# TOMO.net
KiCad netlist of a schematic drawn in EAGLE
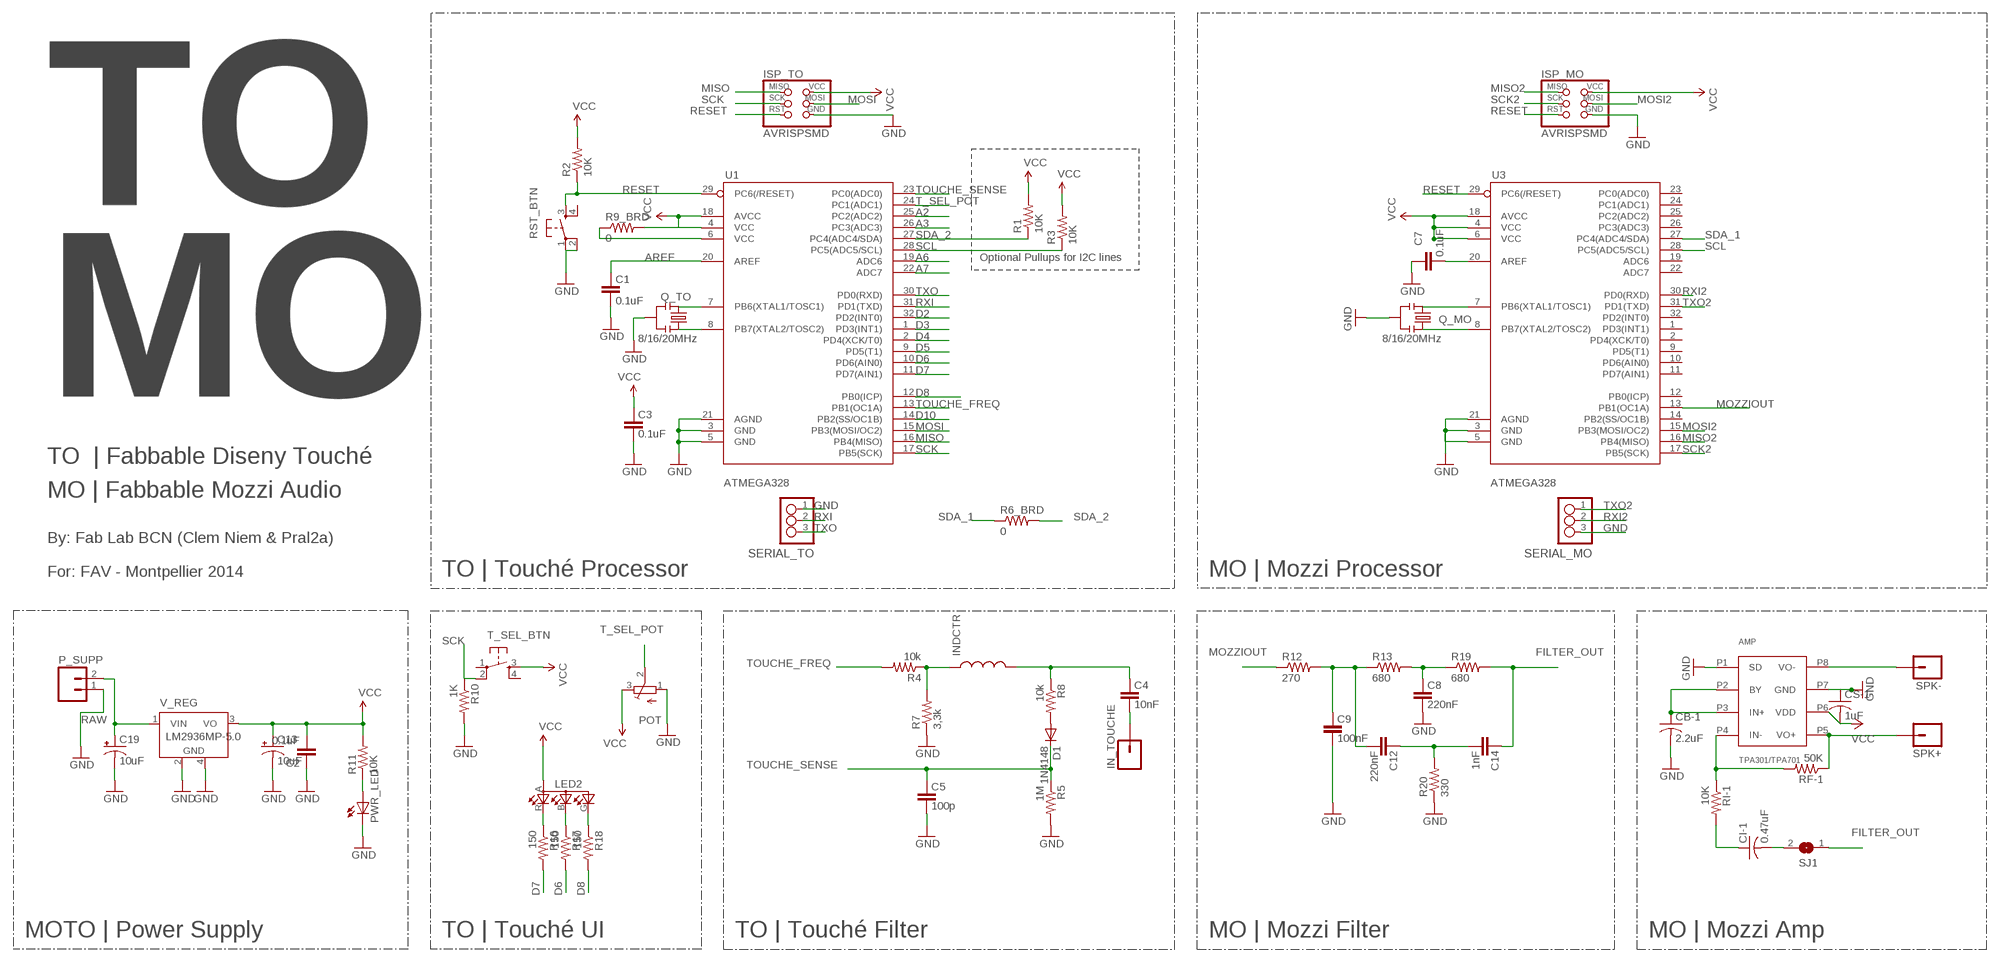
[diagram p0: schematic, sheet 1]

(export (version "E")
  (design (tool "Eeschema 10.0.6"))
  (components
    (comp (ref "AMP")
      (value "TPA301/TPA701")
      (footprint "eagle-import:SOIC8")
      (libsource (lib "eagle-import") (part "TPA301/TPA701"))
    )
    (comp (ref "C1")
      (value "0.1uF")
      (footprint "eagle-import:1206")
      (libsource (lib "eagle-import") (part "CAP1206"))
    )
    (comp (ref "C2")
      (value "0.1uF")
      (footprint "eagle-import:1206")
      (libsource (lib "eagle-import") (part "CAP1206"))
    )
    (comp (ref "C3")
      (value "0.1uF")
      (footprint "eagle-import:1206")
      (libsource (lib "eagle-import") (part "CAP1206"))
    )
    (comp (ref "C4")
      (value "10nF")
      (footprint "eagle-import:1206")
      (libsource (lib "eagle-import") (part "CAP1206"))
    )
    (comp (ref "C5")
      (value "100p")
      (footprint "eagle-import:1206")
      (libsource (lib "eagle-import") (part "CAP1206"))
    )
    (comp (ref "C7")
      (value "0.1uF")
      (footprint "eagle-import:1206")
      (libsource (lib "eagle-import") (part "CAP1206"))
    )
    (comp (ref "C8")
      (value "220nF")
      (footprint "eagle-import:1206")
      (libsource (lib "eagle-import") (part "CAP1206"))
    )
    (comp (ref "C9")
      (value "100nF")
      (footprint "eagle-import:1206")
      (libsource (lib "eagle-import") (part "CAP1206"))
    )
    (comp (ref "C12")
      (value "220nF")
      (footprint "eagle-import:1206")
      (libsource (lib "eagle-import") (part "CAP1206"))
    )
    (comp (ref "C13")
      (value "10uF")
      (footprint "eagle-import:EIA3216")
      (libsource (lib "eagle-import") (part "CAP_POL1206"))
    )
    (comp (ref "C14")
      (value "1nF")
      (footprint "eagle-import:1206")
      (libsource (lib "eagle-import") (part "CAP1206"))
    )
    (comp (ref "C19")
      (value "10uF")
      (footprint "eagle-import:EIA3216")
      (libsource (lib "eagle-import") (part "CAP_POL1206"))
    )
    (comp (ref "CB-1")
      (value "2.2uF")
      (footprint "eagle-import:C1206")
      (libsource (lib "eagle-import") (part "C-USC1206"))
    )
    (comp (ref "CI-1")
      (value "0.47uF")
      (footprint "eagle-import:C1206")
      (libsource (lib "eagle-import") (part "C-USC1206"))
    )
    (comp (ref "CS-1")
      (value "1uF")
      (footprint "eagle-import:C1206")
      (libsource (lib "eagle-import") (part "C-USC1206"))
    )
    (comp (ref "D1")
      (value "1N4148")
      (footprint "eagle-import:SOD123")
      (libsource (lib "eagle-import") (part "DIODESOD123"))
    )
    (comp (ref "INDCTR")
      (value "INDUCTOR")
      (footprint "eagle-import:CDRH3D28")
      (libsource (lib "eagle-import") (part "INDUCTOR"))
    )
    (comp (ref "IN_TOUCHE")
      (value "M01PTH")
      (footprint "eagle-import:1X01")
      (libsource (lib "eagle-import") (part "M01PTH"))
    )
    (comp (ref "ISP_MO")
      (value "AVRISPSMD")
      (footprint "eagle-import:2X03SMD")
      (libsource (lib "eagle-import") (part "AVRISPSMD"))
    )
    (comp (ref "ISP_TO")
      (value "AVRISPSMD")
      (footprint "eagle-import:2X03SMD")
      (libsource (lib "eagle-import") (part "AVRISPSMD"))
    )
    (comp (ref "LED2")
      (value "LEDRGBOLD")
      (footprint "eagle-import:P-LCC-4-3")
      (libsource (lib "eagle-import") (part "LEDRGBOLD"))
    )
    (comp (ref "POT")
      (value "TRIMPOTTC33X")
      (footprint "eagle-import:TC33X")
      (libsource (lib "eagle-import") (part "TRIMPOTTC33X"))
    )
    (comp (ref "PWR_LED")
      (value "LED1206")
      (footprint "eagle-import:1206")
      (libsource (lib "eagle-import") (part "LED1206"))
    )
    (comp (ref "P_SUPP")
      (value "M02PTH")
      (footprint "eagle-import:1X02")
      (libsource (lib "eagle-import") (part "M02PTH"))
    )
    (comp (ref "Q_MO")
      (value "8/16/20MHz")
      (footprint "eagle-import:RESONATOR-SMD")
      (libsource (lib "eagle-import") (part "RESONATORSMD"))
    )
    (comp (ref "Q_TO")
      (value "8/16/20MHz")
      (footprint "eagle-import:RESONATOR-SMD")
      (libsource (lib "eagle-import") (part "RESONATORSMD"))
    )
    (comp (ref "R1")
      (value "10K")
      (footprint "eagle-import:1206")
      (libsource (lib "eagle-import") (part "RESISTOR1206"))
    )
    (comp (ref "R2")
      (value "10K")
      (footprint "eagle-import:1206")
      (libsource (lib "eagle-import") (part "RESISTOR1206"))
    )
    (comp (ref "R3")
      (value "10K")
      (footprint "eagle-import:1206")
      (libsource (lib "eagle-import") (part "RESISTOR1206"))
    )
    (comp (ref "R4")
      (value "10k")
      (footprint "eagle-import:1206")
      (libsource (lib "eagle-import") (part "RESISTOR1206"))
    )
    (comp (ref "R5")
      (value "1M")
      (footprint "eagle-import:1206")
      (libsource (lib "eagle-import") (part "RESISTOR1206"))
    )
    (comp (ref "R6_BRD")
      (value "0")
      (footprint "eagle-import:1206")
      (libsource (lib "eagle-import") (part "RESISTOR1206"))
    )
    (comp (ref "R7")
      (value "3,3k")
      (footprint "eagle-import:1206")
      (libsource (lib "eagle-import") (part "RESISTOR1206"))
    )
    (comp (ref "R8")
      (value "10k")
      (footprint "eagle-import:1206")
      (libsource (lib "eagle-import") (part "RESISTOR1206"))
    )
    (comp (ref "R9_BRD")
      (value "0")
      (footprint "eagle-import:1206")
      (libsource (lib "eagle-import") (part "RESISTOR1206"))
    )
    (comp (ref "R10")
      (value "1K")
      (footprint "eagle-import:1206")
      (libsource (lib "eagle-import") (part "RESISTOR1206"))
    )
    (comp (ref "R11")
      (value "10K")
      (footprint "eagle-import:1206")
      (libsource (lib "eagle-import") (part "RESISTOR1206"))
    )
    (comp (ref "R12")
      (value "270")
      (footprint "eagle-import:1206")
      (libsource (lib "eagle-import") (part "RESISTOR1206"))
    )
    (comp (ref "R13")
      (value "680")
      (footprint "eagle-import:1206")
      (libsource (lib "eagle-import") (part "RESISTOR1206"))
    )
    (comp (ref "R16")
      (value "150")
      (footprint "eagle-import:1206")
      (libsource (lib "eagle-import") (part "RESISTOR1206"))
    )
    (comp (ref "R17")
      (value "150")
      (footprint "eagle-import:1206")
      (libsource (lib "eagle-import") (part "RESISTOR1206"))
    )
    (comp (ref "R18")
      (value "150")
      (footprint "eagle-import:1206")
      (libsource (lib "eagle-import") (part "RESISTOR1206"))
    )
    (comp (ref "R19")
      (value "680")
      (footprint "eagle-import:1206")
      (libsource (lib "eagle-import") (part "RESISTOR1206"))
    )
    (comp (ref "R20")
      (value "330")
      (footprint "eagle-import:0603-RES")
      (libsource (lib "eagle-import") (part "RESISTOR0603-RES"))
    )
    (comp (ref "RF-1")
      (value "50K")
      (footprint "eagle-import:R1206")
      (libsource (lib "eagle-import") (part "R-US_R1206"))
    )
    (comp (ref "RI-1")
      (value "10K")
      (footprint "eagle-import:R1206")
      (libsource (lib "eagle-import") (part "R-US_R1206"))
    )
    (comp (ref "RST_BTN")
      (value "6MM_SWITCH6MM_SWITCH")
      (footprint "eagle-import:6MM_SWITCH")
      (libsource (lib "eagle-import") (part "6MM_SWITCH6MM_SWITCH"))
    )
    (comp (ref "SERIAL_MO")
      (value "3_PIN_HEADERHEADER")
      (footprint "eagle-import:SMT_PINS_3")
      (libsource (lib "eagle-import") (part "3_PIN_HEADERHEADER"))
    )
    (comp (ref "SERIAL_TO")
      (value "3_PIN_HEADERHEADER")
      (footprint "eagle-import:SMT_PINS_3")
      (libsource (lib "eagle-import") (part "3_PIN_HEADERHEADER"))
    )
    (comp (ref "SJ1")
      (value "SJW")
      (footprint "eagle-import:SJW")
      (libsource (lib "eagle-import") (part "SJW"))
    )
    (comp (ref "SPK+")
      (value "M01PTH")
      (footprint "eagle-import:1X01")
      (libsource (lib "eagle-import") (part "M01PTH"))
    )
    (comp (ref "SPK-")
      (value "M01PTH")
      (footprint "eagle-import:1X01")
      (libsource (lib "eagle-import") (part "M01PTH"))
    )
    (comp (ref "T_SEL_BTN")
      (value "6MM_SWITCH6MM_SWITCH")
      (footprint "eagle-import:6MM_SWITCH")
      (libsource (lib "eagle-import") (part "6MM_SWITCH6MM_SWITCH"))
    )
    (comp (ref "U1")
      (value "ATMEGA328")
      (footprint "eagle-import:ATMEGA88THIN")
      (libsource (lib "eagle-import") (part "ATMEGA168ATMEGA88THIN"))
    )
    (comp (ref "U3")
      (value "ATMEGA328")
      (footprint "eagle-import:ATMEGA88THIN")
      (libsource (lib "eagle-import") (part "ATMEGA168ATMEGA88THIN"))
    )
    (comp (ref "V_REG")
      (value "LM2936MP-5.0")
      (footprint "eagle-import:SOT223")
      (fields (field (name "MF") "NATIONAL SEMICONDUCTOR") (field (name "MPN") "LM2936MP-5.0/NOPB"))
      (libsource (lib "eagle-import") (part "LM2936MP?-5.0"))
    )
  )
  (nets
    (net (code "1") (name "/A2") (class "Default")
      (node (ref "U1") (pin "25") (pinfunction "PC2(ADC2)_25") (pintype "bidirectional"))
    )
    (net (code "2") (name "/A3") (class "Default")
      (node (ref "U1") (pin "26") (pinfunction "PC3(ADC3)_26") (pintype "bidirectional"))
    )
    (net (code "3") (name "/A6") (class "Default")
      (node (ref "U1") (pin "19") (pinfunction "ADC6_19") (pintype "bidirectional"))
    )
    (net (code "4") (name "/A7") (class "Default")
      (node (ref "U1") (pin "22") (pinfunction "ADC7_22") (pintype "bidirectional"))
    )
    (net (code "5") (name "/AREF") (class "Default")
      (node (ref "C1") (pin "2") (pinfunction "2_2") (pintype "passive"))
      (node (ref "U1") (pin "20") (pinfunction "AREF_20") (pintype "bidirectional"))
    )
    (net (code "6") (name "/D2") (class "Default")
      (node (ref "U1") (pin "32") (pinfunction "PD2(INT0)_32") (pintype "bidirectional"))
    )
    (net (code "7") (name "/D3") (class "Default")
      (node (ref "U1") (pin "1") (pinfunction "PD3(INT1)_1") (pintype "bidirectional"))
    )
    (net (code "8") (name "/D4") (class "Default")
      (node (ref "U1") (pin "2") (pinfunction "PD4(XCK/T0)_2") (pintype "bidirectional"))
    )
    (net (code "9") (name "/D5") (class "Default")
      (node (ref "U1") (pin "9") (pinfunction "PD5(T1)_9") (pintype "bidirectional"))
    )
    (net (code "10") (name "/D6") (class "Default")
      (node (ref "R17") (pin "2") (pinfunction "2_2") (pintype "passive"))
      (node (ref "U1") (pin "10") (pinfunction "PD6(AIN0)_10") (pintype "bidirectional"))
    )
    (net (code "11") (name "/D7") (class "Default")
      (node (ref "R16") (pin "2") (pinfunction "2_2") (pintype "passive"))
      (node (ref "U1") (pin "11") (pinfunction "PD7(AIN1)_11") (pintype "bidirectional"))
    )
    (net (code "12") (name "/D8") (class "Default")
      (node (ref "R18") (pin "2") (pinfunction "2_2") (pintype "passive"))
      (node (ref "U1") (pin "12") (pinfunction "PB0(ICP)_12") (pintype "bidirectional"))
    )
    (net (code "13") (name "/D10") (class "Default")
      (node (ref "U1") (pin "14") (pinfunction "PB2(SS/OC1B)_14") (pintype "bidirectional"))
    )
    (net (code "14") (name "/FILTER_OUT") (class "Default")
      (node (ref "C14") (pin "2") (pinfunction "2_2") (pintype "passive"))
      (node (ref "R19") (pin "2") (pinfunction "2_2") (pintype "passive"))
      (node (ref "SJ1") (pin "1") (pinfunction "1_1") (pintype "passive"))
    )
    (net (code "15") (name "/MISO") (class "Default")
      (node (ref "ISP_TO") (pin "1") (pinfunction "MISO_1") (pintype "passive"))
      (node (ref "U1") (pin "16") (pinfunction "PB4(MISO)_16") (pintype "bidirectional"))
    )
    (net (code "16") (name "/MISO2") (class "Default")
      (node (ref "ISP_MO") (pin "1") (pinfunction "MISO_1") (pintype "passive"))
      (node (ref "U3") (pin "16") (pinfunction "PB4(MISO)_16") (pintype "bidirectional"))
    )
    (net (code "17") (name "/MOSI") (class "Default")
      (node (ref "ISP_TO") (pin "4") (pinfunction "MOSI_4") (pintype "passive"))
      (node (ref "U1") (pin "15") (pinfunction "PB3(MOSI/OC2)_15") (pintype "bidirectional"))
    )
    (net (code "18") (name "/MOSI2") (class "Default")
      (node (ref "ISP_MO") (pin "4") (pinfunction "MOSI_4") (pintype "passive"))
      (node (ref "U3") (pin "15") (pinfunction "PB3(MOSI/OC2)_15") (pintype "bidirectional"))
    )
    (net (code "19") (name "/MOZZIOUT") (class "Default")
      (node (ref "R12") (pin "1") (pinfunction "1_1") (pintype "passive"))
      (node (ref "U3") (pin "13") (pinfunction "PB1(OC1A)_13") (pintype "bidirectional"))
    )
    (net (code "20") (name "/RAW") (class "Default")
      (node (ref "C19") (pin "A") (pinfunction "+_A") (pintype "passive"))
      (node (ref "P_SUPP") (pin "2") (pinfunction "2_2") (pintype "passive"))
      (node (ref "V_REG") (pin "1") (pinfunction "VIN_1") (pintype "input"))
    )
    (net (code "21") (name "/RESET") (class "Default")
      (node (ref "ISP_MO") (pin "5") (pinfunction "RST_5") (pintype "passive"))
      (node (ref "ISP_TO") (pin "5") (pinfunction "RST_5") (pintype "passive"))
      (node (ref "R2") (pin "1") (pinfunction "1_1") (pintype "passive"))
      (node (ref "RST_BTN") (pin "3") (pinfunction "S_3") (pintype "passive"))
      (node (ref "U1") (pin "29") (pinfunction "PC6(/RESET)_29") (pintype "bidirectional"))
      (node (ref "U3") (pin "29") (pinfunction "PC6(/RESET)_29") (pintype "bidirectional"))
    )
    (net (code "22") (name "/RXI") (class "Default")
      (node (ref "SERIAL_TO") (pin "2") (pinfunction "P$2_2") (pintype "bidirectional"))
      (node (ref "U1") (pin "31") (pinfunction "PD1(TXD)_31") (pintype "bidirectional"))
    )
    (net (code "23") (name "/RXI2") (class "Default")
      (node (ref "SERIAL_MO") (pin "2") (pinfunction "P$2_2") (pintype "bidirectional"))
      (node (ref "U3") (pin "30") (pinfunction "PD0(RXD)_30") (pintype "bidirectional"))
    )
    (net (code "24") (name "/SCK") (class "Default")
      (node (ref "ISP_TO") (pin "3") (pinfunction "SCK_3") (pintype "passive"))
      (node (ref "R10") (pin "1") (pinfunction "1_1") (pintype "passive"))
      (node (ref "T_SEL_BTN") (pin "2") (pinfunction "P1_2") (pintype "passive"))
      (node (ref "U1") (pin "17") (pinfunction "PB5(SCK)_17") (pintype "bidirectional"))
    )
    (net (code "25") (name "/SCK2") (class "Default")
      (node (ref "ISP_MO") (pin "3") (pinfunction "SCK_3") (pintype "passive"))
      (node (ref "U3") (pin "17") (pinfunction "PB5(SCK)_17") (pintype "bidirectional"))
    )
    (net (code "26") (name "/SCL") (class "Default")
      (node (ref "R3") (pin "1") (pinfunction "1_1") (pintype "passive"))
      (node (ref "U1") (pin "28") (pinfunction "PC5(ADC5/SCL)_28") (pintype "bidirectional"))
      (node (ref "U3") (pin "28") (pinfunction "PC5(ADC5/SCL)_28") (pintype "bidirectional"))
    )
    (net (code "27") (name "/SDA_1") (class "Default")
      (node (ref "R6_BRD") (pin "1") (pinfunction "1_1") (pintype "passive"))
      (node (ref "U3") (pin "27") (pinfunction "PC4(ADC4/SDA)_27") (pintype "bidirectional"))
    )
    (net (code "28") (name "/SDA_2") (class "Default")
      (node (ref "R1") (pin "1") (pinfunction "1_1") (pintype "passive"))
      (node (ref "R6_BRD") (pin "2") (pinfunction "2_2") (pintype "passive"))
      (node (ref "U1") (pin "27") (pinfunction "PC4(ADC4/SDA)_27") (pintype "bidirectional"))
    )
    (net (code "29") (name "/TOUCHE_FREQ") (class "Default")
      (node (ref "R4") (pin "2") (pinfunction "2_2") (pintype "passive"))
      (node (ref "U1") (pin "13") (pinfunction "PB1(OC1A)_13") (pintype "bidirectional"))
    )
    (net (code "30") (name "/TOUCHE_SENSE") (class "Default")
      (node (ref "C5") (pin "2") (pinfunction "2_2") (pintype "passive"))
      (node (ref "D1") (pin "CATHODE") (pinfunction "C_CATHODE") (pintype "passive"))
      (node (ref "R5") (pin "1") (pinfunction "1_1") (pintype "passive"))
      (node (ref "U1") (pin "23") (pinfunction "PC0(ADC0)_23") (pintype "bidirectional"))
    )
    (net (code "31") (name "/TXO") (class "Default")
      (node (ref "SERIAL_TO") (pin "3") (pinfunction "P$3_3") (pintype "bidirectional"))
      (node (ref "U1") (pin "30") (pinfunction "PD0(RXD)_30") (pintype "bidirectional"))
    )
    (net (code "32") (name "/TXO2") (class "Default")
      (node (ref "SERIAL_MO") (pin "1") (pinfunction "P$1_1") (pintype "bidirectional"))
      (node (ref "U3") (pin "31") (pinfunction "PD1(TXD)_31") (pintype "bidirectional"))
    )
    (net (code "33") (name "/T_SEL_POT") (class "Default")
      (node (ref "POT") (pin "2") (pinfunction "S_2") (pintype "passive"))
      (node (ref "U1") (pin "24") (pinfunction "PC1(ADC1)_24") (pintype "bidirectional"))
    )
    (net (code "34") (name "GND") (class "Default")
      (node (ref "AMP") (pin "P1") (pinfunction "SD_P1") (pintype "bidirectional"))
      (node (ref "AMP") (pin "P7") (pinfunction "GND_P7") (pintype "bidirectional"))
      (node (ref "C1") (pin "1") (pinfunction "1_1") (pintype "passive"))
      (node (ref "C13") (pin "C") (pinfunction "-_C") (pintype "passive"))
      (node (ref "C19") (pin "C") (pinfunction "-_C") (pintype "passive"))
      (node (ref "C2") (pin "1") (pinfunction "1_1") (pintype "passive"))
      (node (ref "C3") (pin "1") (pinfunction "1_1") (pintype "passive"))
      (node (ref "C5") (pin "1") (pinfunction "1_1") (pintype "passive"))
      (node (ref "C7") (pin "2") (pinfunction "2_2") (pintype "passive"))
      (node (ref "C8") (pin "1") (pinfunction "1_1") (pintype "passive"))
      (node (ref "C9") (pin "1") (pinfunction "1_1") (pintype "passive"))
      (node (ref "CB-1") (pin "2") (pinfunction "2_2") (pintype "passive"))
      (node (ref "CS-1") (pin "1") (pinfunction "1_1") (pintype "passive"))
      (node (ref "ISP_MO") (pin "6") (pinfunction "GND_6") (pintype "passive"))
      (node (ref "ISP_TO") (pin "6") (pinfunction "GND_6") (pintype "passive"))
      (node (ref "POT") (pin "1") (pinfunction "A_1") (pintype "passive"))
      (node (ref "PWR_LED") (pin "2") (pinfunction "C_2") (pintype "passive"))
      (node (ref "P_SUPP") (pin "1") (pinfunction "1_1") (pintype "passive"))
      (node (ref "Q_MO") (pin "2") (pinfunction "2_2") (pintype "passive"))
      (node (ref "Q_TO") (pin "2") (pinfunction "2_2") (pintype "passive"))
      (node (ref "R10") (pin "2") (pinfunction "2_2") (pintype "passive"))
      (node (ref "R20") (pin "1") (pinfunction "1_1") (pintype "passive"))
      (node (ref "R5") (pin "2") (pinfunction "2_2") (pintype "passive"))
      (node (ref "R7") (pin "1") (pinfunction "1_1") (pintype "passive"))
      (node (ref "RST_BTN") (pin "1") (pinfunction "P_1") (pintype "passive"))
      (node (ref "RST_BTN") (pin "2") (pinfunction "P1_2") (pintype "passive"))
      (node (ref "SERIAL_MO") (pin "3") (pinfunction "P$3_3") (pintype "bidirectional"))
      (node (ref "SERIAL_TO") (pin "1") (pinfunction "P$1_1") (pintype "bidirectional"))
      (node (ref "U1") (pin "21") (pinfunction "AGND_21") (pintype "bidirectional"))
      (node (ref "U1") (pin "3") (pinfunction "GND_3") (pintype "bidirectional"))
      (node (ref "U1") (pin "5") (pinfunction "GND_5") (pintype "bidirectional"))
      (node (ref "U3") (pin "21") (pinfunction "AGND_21") (pintype "bidirectional"))
      (node (ref "U3") (pin "3") (pinfunction "GND_3") (pintype "bidirectional"))
      (node (ref "U3") (pin "5") (pinfunction "GND_5") (pintype "bidirectional"))
      (node (ref "V_REG") (pin "2") (pinfunction "GND_2") (pintype "passive"))
      (node (ref "V_REG") (pin "4") (pinfunction "GND_4") (pintype "passive"))
    )
    (net (code "35") (name "Net-(AMP-BY)") (class "Default")
      (node (ref "AMP") (pin "P2") (pinfunction "BY_P2") (pintype "bidirectional"))
      (node (ref "AMP") (pin "P3") (pinfunction "IN+_P3") (pintype "bidirectional"))
      (node (ref "CB-1") (pin "1") (pinfunction "1_1") (pintype "passive"))
    )
    (net (code "36") (name "Net-(AMP-IN-)") (class "Default")
      (node (ref "AMP") (pin "P4") (pinfunction "IN-_P4") (pintype "bidirectional"))
      (node (ref "RF-1") (pin "2") (pinfunction "2_2") (pintype "passive"))
      (node (ref "RI-1") (pin "1") (pinfunction "1_1") (pintype "passive"))
    )
    (net (code "37") (name "Net-(AMP-VO+)") (class "Default")
      (node (ref "AMP") (pin "P5") (pinfunction "VO+_P5") (pintype "bidirectional"))
      (node (ref "RF-1") (pin "1") (pinfunction "1_1") (pintype "passive"))
      (node (ref "SPK+") (pin "1") (pinfunction "1_1") (pintype "passive"))
    )
    (net (code "38") (name "Net-(AMP-VO-)") (class "Default")
      (node (ref "AMP") (pin "P8") (pinfunction "VO-_P8") (pintype "bidirectional"))
      (node (ref "SPK-") (pin "1") (pinfunction "1_1") (pintype "passive"))
    )
    (net (code "39") (name "Net-(C4-Pad1)") (class "Default")
      (node (ref "C4") (pin "1") (pinfunction "1_1") (pintype "passive"))
      (node (ref "IN_TOUCHE") (pin "1") (pinfunction "1_1") (pintype "passive"))
    )
    (net (code "40") (name "Net-(C4-Pad2)") (class "Default")
      (node (ref "C4") (pin "2") (pinfunction "2_2") (pintype "passive"))
      (node (ref "INDCTR") (pin "2") (pinfunction "2_2") (pintype "passive"))
      (node (ref "R8") (pin "1") (pinfunction "1_1") (pintype "passive"))
    )
    (net (code "41") (name "Net-(C8-Pad2)") (class "Default")
      (node (ref "C8") (pin "2") (pinfunction "2_2") (pintype "passive"))
      (node (ref "R13") (pin "2") (pinfunction "2_2") (pintype "passive"))
      (node (ref "R19") (pin "1") (pinfunction "1_1") (pintype "passive"))
    )
    (net (code "42") (name "Net-(C12-Pad1)") (class "Default")
      (node (ref "C12") (pin "1") (pinfunction "1_1") (pintype "passive"))
      (node (ref "C9") (pin "2") (pinfunction "2_2") (pintype "passive"))
      (node (ref "R12") (pin "2") (pinfunction "2_2") (pintype "passive"))
      (node (ref "R13") (pin "1") (pinfunction "1_1") (pintype "passive"))
    )
    (net (code "43") (name "Net-(C12-Pad2)") (class "Default")
      (node (ref "C12") (pin "2") (pinfunction "2_2") (pintype "passive"))
      (node (ref "C14") (pin "1") (pinfunction "1_1") (pintype "passive"))
      (node (ref "R20") (pin "2") (pinfunction "2_2") (pintype "passive"))
    )
    (net (code "44") (name "Net-(CI-1-Pad1)") (class "Default")
      (node (ref "CI-1") (pin "1") (pinfunction "1_1") (pintype "passive"))
      (node (ref "RI-1") (pin "2") (pinfunction "2_2") (pintype "passive"))
    )
    (net (code "45") (name "Net-(CI-1-Pad2)") (class "Default")
      (node (ref "CI-1") (pin "2") (pinfunction "2_2") (pintype "passive"))
      (node (ref "SJ1") (pin "2") (pinfunction "2_2") (pintype "passive"))
    )
    (net (code "46") (name "Net-(D1-A)") (class "Default")
      (node (ref "D1") (pin "ANODE") (pinfunction "A_ANODE") (pintype "passive"))
      (node (ref "R8") (pin "2") (pinfunction "2_2") (pintype "passive"))
    )
    (net (code "47") (name "Net-(INDCTR-Pad1)") (class "Default")
      (node (ref "INDCTR") (pin "1") (pinfunction "1_1") (pintype "passive"))
      (node (ref "R4") (pin "1") (pinfunction "1_1") (pintype "passive"))
      (node (ref "R7") (pin "2") (pinfunction "2_2") (pintype "passive"))
    )
    (net (code "48") (name "Net-(LED2-CBLUE)") (class "Default")
      (node (ref "LED2") (pin "B") (pinfunction "CBLUE_B") (pintype "passive"))
      (node (ref "R17") (pin "1") (pinfunction "1_1") (pintype "passive"))
    )
    (net (code "49") (name "Net-(LED2-CGREEN)") (class "Default")
      (node (ref "LED2") (pin "G") (pinfunction "CGREEN_G") (pintype "passive"))
      (node (ref "R18") (pin "1") (pinfunction "1_1") (pintype "passive"))
    )
    (net (code "50") (name "Net-(LED2-CRED)") (class "Default")
      (node (ref "LED2") (pin "R") (pinfunction "CRED_R") (pintype "passive"))
      (node (ref "R16") (pin "1") (pinfunction "1_1") (pintype "passive"))
    )
    (net (code "51") (name "Net-(PWR_LED-A)") (class "Default")
      (node (ref "PWR_LED") (pin "1") (pinfunction "A_1") (pintype "passive"))
      (node (ref "R11") (pin "1") (pinfunction "1_1") (pintype "passive"))
    )
    (net (code "52") (name "Net-(R9_BRD-Pad1)") (class "Default")
      (node (ref "R9_BRD") (pin "1") (pinfunction "1_1") (pintype "passive"))
      (node (ref "U1") (pin "6") (pinfunction "VCC_6") (pintype "bidirectional"))
    )
    (net (code "53") (name "Net-(U1-PB6(XTAL1{slash}TOSC1))") (class "Default")
      (node (ref "Q_TO") (pin "3") (pinfunction "3_3") (pintype "passive"))
      (node (ref "U1") (pin "7") (pinfunction "PB6(XTAL1/TOSC1)_7") (pintype "bidirectional"))
    )
    (net (code "54") (name "Net-(U1-PB7(XTAL2{slash}TOSC2))") (class "Default")
      (node (ref "Q_TO") (pin "1") (pinfunction "1_1") (pintype "passive"))
      (node (ref "U1") (pin "8") (pinfunction "PB7(XTAL2/TOSC2)_8") (pintype "bidirectional"))
    )
    (net (code "55") (name "Net-(U3-AREF)") (class "Default")
      (node (ref "C7") (pin "1") (pinfunction "1_1") (pintype "passive"))
      (node (ref "U3") (pin "20") (pinfunction "AREF_20") (pintype "bidirectional"))
    )
    (net (code "56") (name "Net-(U3-PB6(XTAL1{slash}TOSC1))") (class "Default")
      (node (ref "Q_MO") (pin "3") (pinfunction "3_3") (pintype "passive"))
      (node (ref "U3") (pin "7") (pinfunction "PB6(XTAL1/TOSC1)_7") (pintype "bidirectional"))
    )
    (net (code "57") (name "Net-(U3-PB7(XTAL2{slash}TOSC2))") (class "Default")
      (node (ref "Q_MO") (pin "1") (pinfunction "1_1") (pintype "passive"))
      (node (ref "U3") (pin "8") (pinfunction "PB7(XTAL2/TOSC2)_8") (pintype "bidirectional"))
    )
    (net (code "58") (name "VCC") (class "Default")
      (node (ref "AMP") (pin "P6") (pinfunction "VDD_P6") (pintype "bidirectional"))
      (node (ref "C13") (pin "A") (pinfunction "+_A") (pintype "passive"))
      (node (ref "C2") (pin "2") (pinfunction "2_2") (pintype "passive"))
      (node (ref "C3") (pin "2") (pinfunction "2_2") (pintype "passive"))
      (node (ref "CS-1") (pin "2") (pinfunction "2_2") (pintype "passive"))
      (node (ref "ISP_MO") (pin "2") (pinfunction "VCC_2") (pintype "passive"))
      (node (ref "ISP_TO") (pin "2") (pinfunction "VCC_2") (pintype "passive"))
      (node (ref "LED2") (pin "A") (pinfunction "A2_A") (pintype "passive"))
      (node (ref "POT") (pin "3") (pinfunction "E_3") (pintype "passive"))
      (node (ref "R1") (pin "2") (pinfunction "2_2") (pintype "passive"))
      (node (ref "R11") (pin "2") (pinfunction "2_2") (pintype "passive"))
      (node (ref "R2") (pin "2") (pinfunction "2_2") (pintype "passive"))
      (node (ref "R3") (pin "2") (pinfunction "2_2") (pintype "passive"))
      (node (ref "R9_BRD") (pin "2") (pinfunction "2_2") (pintype "passive"))
      (node (ref "T_SEL_BTN") (pin "3") (pinfunction "S_3") (pintype "passive"))
      (node (ref "U1") (pin "18") (pinfunction "AVCC_18") (pintype "bidirectional"))
      (node (ref "U1") (pin "4") (pinfunction "VCC_4") (pintype "bidirectional"))
      (node (ref "U3") (pin "18") (pinfunction "AVCC_18") (pintype "bidirectional"))
      (node (ref "U3") (pin "4") (pinfunction "VCC_4") (pintype "bidirectional"))
      (node (ref "U3") (pin "6") (pinfunction "VCC_6") (pintype "bidirectional"))
      (node (ref "V_REG") (pin "3") (pinfunction "VO_3") (pintype "passive"))
    )
    (net (code "59") (name "unconnected-(RST_BTN-S1-Pad4)") (class "Default")
      (node (ref "RST_BTN") (pin "4") (pinfunction "S1_4") (pintype "passive"))
    )
    (net (code "60") (name "unconnected-(T_SEL_BTN-P-Pad1)") (class "Default")
      (node (ref "T_SEL_BTN") (pin "1") (pinfunction "P_1") (pintype "passive"))
    )
    (net (code "61") (name "unconnected-(T_SEL_BTN-S1-Pad4)") (class "Default")
      (node (ref "T_SEL_BTN") (pin "4") (pinfunction "S1_4") (pintype "passive"))
    )
    (net (code "62") (name "unconnected-(U3-ADC6-Pad19)") (class "Default")
      (node (ref "U3") (pin "19") (pinfunction "ADC6_19") (pintype "bidirectional"))
    )
    (net (code "63") (name "unconnected-(U3-ADC7-Pad22)") (class "Default")
      (node (ref "U3") (pin "22") (pinfunction "ADC7_22") (pintype "bidirectional"))
    )
    (net (code "64") (name "unconnected-(U3-PB0(ICP)-Pad12)") (class "Default")
      (node (ref "U3") (pin "12") (pinfunction "PB0(ICP)_12") (pintype "bidirectional"))
    )
    (net (code "65") (name "unconnected-(U3-PB2(SS{slash}OC1B)-Pad14)") (class "Default")
      (node (ref "U3") (pin "14") (pinfunction "PB2(SS/OC1B)_14") (pintype "bidirectional"))
    )
    (net (code "66") (name "unconnected-(U3-PC0(ADC0)-Pad23)") (class "Default")
      (node (ref "U3") (pin "23") (pinfunction "PC0(ADC0)_23") (pintype "bidirectional"))
    )
    (net (code "67") (name "unconnected-(U3-PC1(ADC1)-Pad24)") (class "Default")
      (node (ref "U3") (pin "24") (pinfunction "PC1(ADC1)_24") (pintype "bidirectional"))
    )
    (net (code "68") (name "unconnected-(U3-PC2(ADC2)-Pad25)") (class "Default")
      (node (ref "U3") (pin "25") (pinfunction "PC2(ADC2)_25") (pintype "bidirectional"))
    )
    (net (code "69") (name "unconnected-(U3-PC3(ADC3)-Pad26)") (class "Default")
      (node (ref "U3") (pin "26") (pinfunction "PC3(ADC3)_26") (pintype "bidirectional"))
    )
    (net (code "70") (name "unconnected-(U3-PD2(INT0)-Pad32)") (class "Default")
      (node (ref "U3") (pin "32") (pinfunction "PD2(INT0)_32") (pintype "bidirectional"))
    )
    (net (code "71") (name "unconnected-(U3-PD3(INT1)-Pad1)") (class "Default")
      (node (ref "U3") (pin "1") (pinfunction "PD3(INT1)_1") (pintype "bidirectional"))
    )
    (net (code "72") (name "unconnected-(U3-PD4(XCK{slash}T0)-Pad2)") (class "Default")
      (node (ref "U3") (pin "2") (pinfunction "PD4(XCK/T0)_2") (pintype "bidirectional"))
    )
    (net (code "73") (name "unconnected-(U3-PD5(T1)-Pad9)") (class "Default")
      (node (ref "U3") (pin "9") (pinfunction "PD5(T1)_9") (pintype "bidirectional"))
    )
    (net (code "74") (name "unconnected-(U3-PD6(AIN0)-Pad10)") (class "Default")
      (node (ref "U3") (pin "10") (pinfunction "PD6(AIN0)_10") (pintype "bidirectional"))
    )
    (net (code "75") (name "unconnected-(U3-PD7(AIN1)-Pad11)") (class "Default")
      (node (ref "U3") (pin "11") (pinfunction "PD7(AIN1)_11") (pintype "bidirectional"))
    )
  )
)
